# CANTRICK_PERIPHERAL.net
KiCad netlist of a schematic drawn in Altium Designer
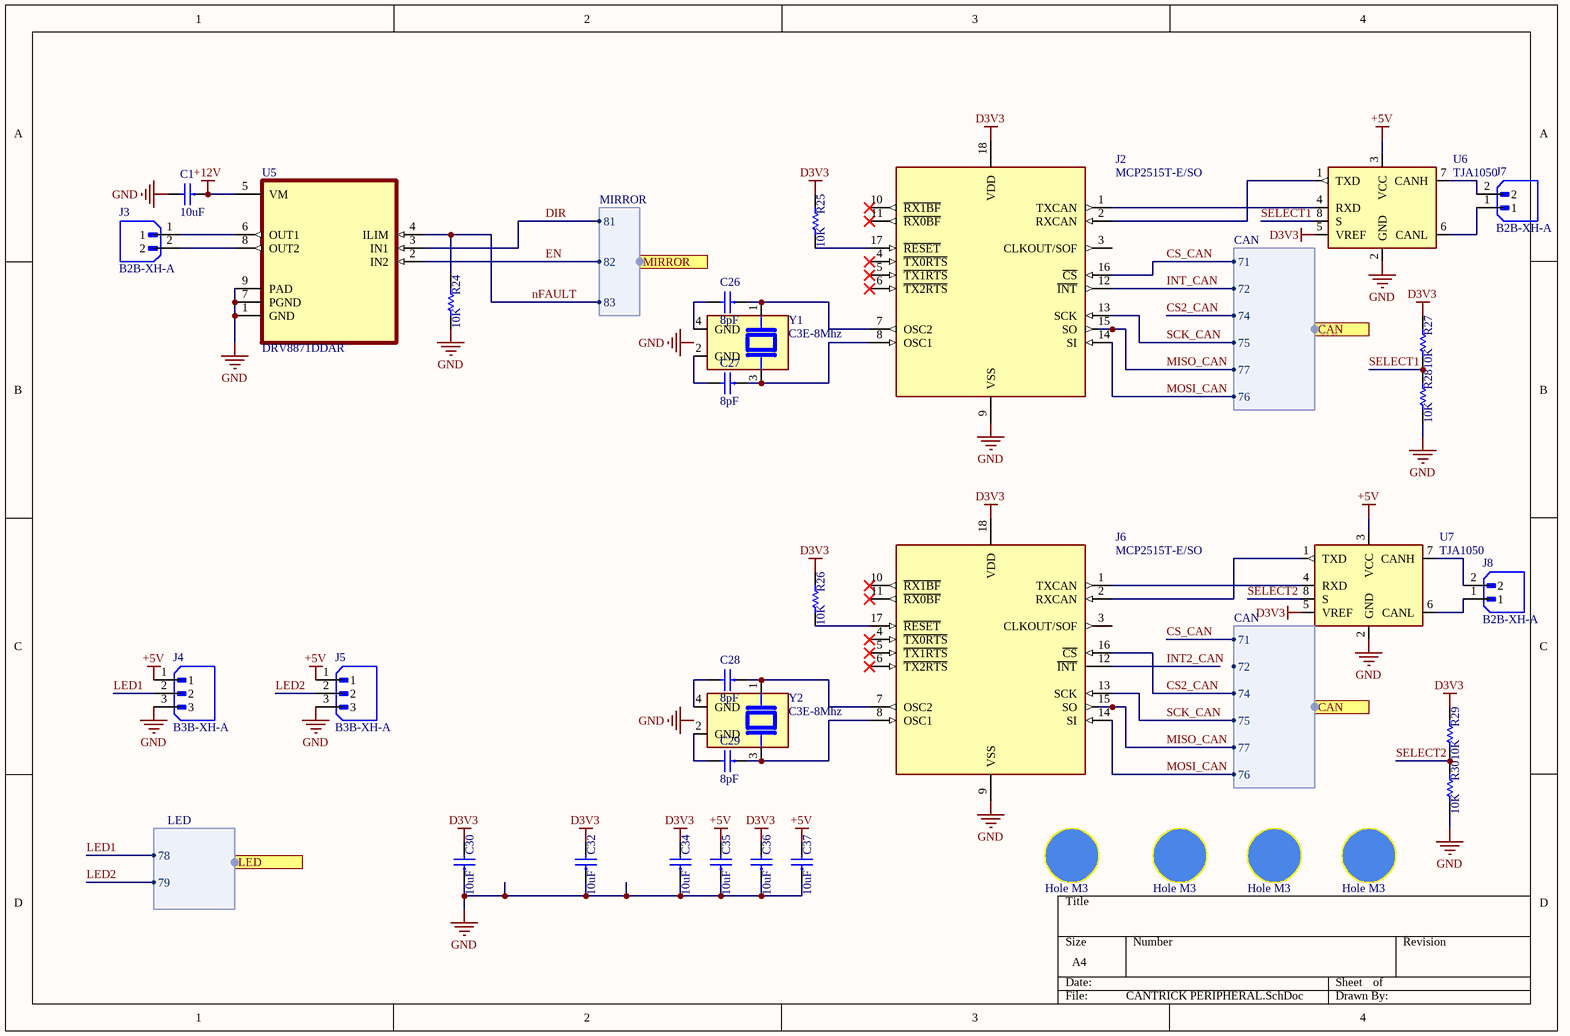
[diagram p0: CANTRICK PERIPHERAL.SchDoc]

(export (version "E")
  (design (tool "Eeschema 10.0.6"))
  (components
    (comp (ref "*1") (value "Hole M3") (footprint "M3") (libsource (lib "POWER_PIN_CAMERA") (part "Hole M3")))
    (comp (ref "*2") (value "Hole M3") (footprint "M3") (libsource (lib "POWER_PIN_CAMERA") (part "Hole M3")))
    (comp (ref "*3") (value "Hole M3") (footprint "M3") (libsource (lib "POWER_PIN_CAMERA") (part "Hole M3")))
    (comp (ref "*4") (value "Hole M3") (footprint "M3") (libsource (lib "POWER_PIN_CAMERA") (part "Hole M3")))
    (comp (ref "C1")
      (value "10uF")
      (footprint "CAP-CER0603-0.8H")
      (description "CAP CER 100nF 10% 50V X7R 0603 SMD")
      (libsource (lib "NAVIGATION") (part "CAPCER0001 100nF 10% 50V X7R 0603 SMD"))
    )
    (comp (ref "C26")
      (value "8pF")
      (footprint "CAP-CER0402-0.5H")
      (description "CAP CER 100nF 10% 50V X7R 0402 SMD")
      (libsource (lib "2502-GMQLITE-MAIN") (part "CAPCER0013 100nF 10% 50V X7R 0402 SMD"))
    )
    (comp (ref "C27")
      (value "8pF")
      (footprint "CAP-CER0402-0.5H")
      (description "CAP CER 100nF 10% 50V X7R 0402 SMD")
      (libsource (lib "2502-GMQLITE-MAIN") (part "CAPCER0013 100nF 10% 50V X7R 0402 SMD"))
    )
    (comp (ref "C28")
      (value "8pF")
      (footprint "CAP-CER0402-0.5H")
      (description "CAP CER 100nF 10% 50V X7R 0402 SMD")
      (libsource (lib "2502-GMQLITE-MAIN") (part "CAPCER0013 100nF 10% 50V X7R 0402 SMD"))
    )
    (comp (ref "C29")
      (value "8pF")
      (footprint "CAP-CER0402-0.5H")
      (description "CAP CER 100nF 10% 50V X7R 0402 SMD")
      (libsource (lib "2502-GMQLITE-MAIN") (part "CAPCER0013 100nF 10% 50V X7R 0402 SMD"))
    )
    (comp (ref "C30")
      (value "10uF")
      (footprint "CAP-CER0603-0.8H")
      (description "CAP CER 100nF 10% 50V X7R 0603 SMD")
      (libsource (lib "NAVIGATION") (part "CAPCER0001 100nF 10% 50V X7R 0603 SMD"))
    )
    (comp (ref "C32")
      (value "10uF")
      (footprint "CAP-CER0603-0.8H")
      (description "CAP CER 100nF 10% 50V X7R 0603 SMD")
      (libsource (lib "NAVIGATION") (part "CAPCER0001 100nF 10% 50V X7R 0603 SMD"))
    )
    (comp (ref "C34")
      (value "10uF")
      (footprint "CAP-CER0603-0.8H")
      (description "CAP CER 100nF 10% 50V X7R 0603 SMD")
      (libsource (lib "NAVIGATION") (part "CAPCER0001 100nF 10% 50V X7R 0603 SMD"))
    )
    (comp (ref "C35")
      (value "10uF")
      (footprint "CAP-CER0603-0.8H")
      (description "CAP CER 100nF 10% 50V X7R 0603 SMD")
      (libsource (lib "NAVIGATION") (part "CAPCER0001 100nF 10% 50V X7R 0603 SMD"))
    )
    (comp (ref "C36")
      (value "10uF")
      (footprint "CAP-CER0603-0.8H")
      (description "CAP CER 100nF 10% 50V X7R 0603 SMD")
      (libsource (lib "NAVIGATION") (part "CAPCER0001 100nF 10% 50V X7R 0603 SMD"))
    )
    (comp (ref "C37")
      (value "10uF")
      (footprint "CAP-CER0603-0.8H")
      (description "CAP CER 100nF 10% 50V X7R 0603 SMD")
      (libsource (lib "NAVIGATION") (part "CAPCER0001 100nF 10% 50V X7R 0603 SMD"))
    )
    (comp (ref "J2")
      (value "MCP2515T-E/SO")
      (footprint "SOIC127P1030X265-18N")
      (fields (field (name "MF") "Microchip"))
      (libsource (lib "MCP2515T-E_SO") (part "MCP2515T-E/SO"))
    )
    (comp (ref "J3")
      (value "B2B-XH-A")
      (footprint "JST_B2B-XH-A")
      (fields (field (name "MF") "{'manufacturer': u'JST Sales America Inc.'}"))
      (libsource (lib "") (part "B2B-XH-A_1"))
    )
    (comp (ref "J4")
      (value "B3B-XH-A")
      (footprint "JST_B3B-XH-A")
      (description "Connector Header Through Hole 3 position 0.098 (2.50mm)")
      (fields (field (name "MF") "JST Sales"))
      (libsource (lib "B3B-XH-A") (part "B3B-XH-A"))
    )
    (comp (ref "J5")
      (value "B3B-XH-A")
      (footprint "JST_B3B-XH-A")
      (description "Connector Header Through Hole 3 position 0.098 (2.50mm)")
      (fields (field (name "MF") "JST Sales"))
      (libsource (lib "B3B-XH-A") (part "B3B-XH-A"))
    )
    (comp (ref "J6")
      (value "MCP2515T-E/SO")
      (footprint "SOIC127P1030X265-18N")
      (fields (field (name "MF") "Microchip"))
      (libsource (lib "MCP2515T-E_SO") (part "MCP2515T-E/SO"))
    )
    (comp (ref "J7")
      (value "B2B-XH-A")
      (footprint "JST_B2B-XH-A")
      (fields (field (name "MF") "{'manufacturer': u'JST Sales America Inc.'}"))
      (libsource (lib "B2B-XH-A") (part "B2B-XH-A"))
    )
    (comp (ref "J8")
      (value "B2B-XH-A")
      (footprint "JST_B2B-XH-A")
      (fields (field (name "MF") "{'manufacturer': u'JST Sales America Inc.'}"))
      (libsource (lib "B2B-XH-A") (part "B2B-XH-A"))
    )
    (comp (ref "R24")
      (value "10K")
      (footprint "Res 0603")
      (description "Res Thick Film 0603 2.2K Ohm 5% 1/10W ±200ppm/°C Molded SMD SMD Paper T/R")
      (fields
        (field (name "MANUFACTURER") "Vishay")
        (field (name "MANUFACTURER PART NUMBER") "CRCW06032K20JNEA")
      )
      (libsource (lib "Stm32_Flyback_Driver_250814_1") (part "Resistor 2.2K"))
    )
    (comp (ref "R25")
      (value "10K")
      (footprint "Res 0603")
      (description "Res Thick Film 0603 2.2K Ohm 5% 1/10W ±200ppm/°C Molded SMD SMD Paper T/R")
      (fields
        (field (name "MANUFACTURER") "Vishay")
        (field (name "MANUFACTURER PART NUMBER") "CRCW06032K20JNEA")
      )
      (libsource (lib "Stm32_Flyback_Driver_250814_1") (part "Resistor 2.2K"))
    )
    (comp (ref "R26")
      (value "10K")
      (footprint "Res 0603")
      (description "Res Thick Film 0603 2.2K Ohm 5% 1/10W ±200ppm/°C Molded SMD SMD Paper T/R")
      (fields
        (field (name "MANUFACTURER") "Vishay")
        (field (name "MANUFACTURER PART NUMBER") "CRCW06032K20JNEA")
      )
      (libsource (lib "Stm32_Flyback_Driver_250814_1") (part "Resistor 2.2K"))
    )
    (comp (ref "R27")
      (value "10K")
      (footprint "Res 0603")
      (description "Res Thick Film 0603 2.2K Ohm 5% 1/10W ±200ppm/°C Molded SMD SMD Paper T/R")
      (fields
        (field (name "MANUFACTURER") "Vishay")
        (field (name "MANUFACTURER PART NUMBER") "CRCW06032K20JNEA")
      )
      (libsource (lib "Stm32_Flyback_Driver_250814_1") (part "Resistor 2.2K"))
    )
    (comp (ref "R28")
      (value "10K")
      (footprint "Res 0603")
      (description "Res Thick Film 0603 2.2K Ohm 5% 1/10W ±200ppm/°C Molded SMD SMD Paper T/R")
      (fields
        (field (name "MANUFACTURER") "Vishay")
        (field (name "MANUFACTURER PART NUMBER") "CRCW06032K20JNEA")
      )
      (libsource (lib "Stm32_Flyback_Driver_250814_1") (part "Resistor 2.2K"))
    )
    (comp (ref "R29")
      (value "10K")
      (footprint "Res 0603")
      (description "Res Thick Film 0603 2.2K Ohm 5% 1/10W ±200ppm/°C Molded SMD SMD Paper T/R")
      (fields
        (field (name "MANUFACTURER") "Vishay")
        (field (name "MANUFACTURER PART NUMBER") "CRCW06032K20JNEA")
      )
      (libsource (lib "Stm32_Flyback_Driver_250814_1") (part "Resistor 2.2K"))
    )
    (comp (ref "R30")
      (value "10K")
      (footprint "Res 0603")
      (description "Res Thick Film 0603 2.2K Ohm 5% 1/10W ±200ppm/°C Molded SMD SMD Paper T/R")
      (fields
        (field (name "MANUFACTURER") "Vishay")
        (field (name "MANUFACTURER PART NUMBER") "CRCW06032K20JNEA")
      )
      (libsource (lib "Stm32_Flyback_Driver_250814_1") (part "Resistor 2.2K"))
    )
    (comp (ref "U5")
      (value "DRV8871DDAR")
      (footprint "VREG_LM5017MR/NOPB")
      (description "50-V, 3.6-A H-bridge motor driver with integrated current sensing")
      (fields (field (name "MF") "Texas Instruments"))
      (libsource (lib "DRV8871DDAR") (part "DRV8871DDAR"))
    )
    (comp (ref "U6")
      (value "TJA1050")
      (footprint "SOT96-1")
      (description "CAN 1MBd Silent 5V Automotive 8-Pin SO T/R")
      (fields (field (name "MF") "NXP Semiconductors"))
      (libsource (lib "TJA1050") (part "TJA1050"))
    )
    (comp (ref "U7")
      (value "TJA1050")
      (footprint "SOT96-1")
      (description "CAN 1MBd Silent 5V Automotive 8-Pin SO T/R")
      (fields (field (name "MF") "NXP Semiconductors"))
      (libsource (lib "TJA1050") (part "TJA1050"))
    )
    (comp (ref "Y1")
      (value "C3E-8Mhz")
      (footprint "XTAL_C3E-8.000-8-1015-R")
      (fields (field (name "MP") "C3E-8.000-8-1015-R"))
      (libsource (lib "C3E-8.000-8-1015-R") (part "C3E-8.000-8-1015-R"))
    )
    (comp (ref "Y2")
      (value "C3E-8Mhz")
      (footprint "XTAL_C3E-8.000-8-1015-R")
      (fields (field (name "MP") "C3E-8.000-8-1015-R"))
      (libsource (lib "C3E-8.000-8-1015-R") (part "C3E-8.000-8-1015-R"))
    )
  )
  (nets
    (net (code "4") (name "+5V") (class "Default")
      (node (ref "C35") (pin "2") (pinfunction "2_2") (pintype "passive"))
      (node (ref "C37") (pin "2") (pinfunction "2_2") (pintype "passive"))
      (node (ref "J4") (pin "1") (pinfunction "1_1") (pintype "passive"))
      (node (ref "J5") (pin "1") (pinfunction "1_1") (pintype "passive"))
      (node (ref "U6") (pin "3") (pinfunction "VCC_3") (pintype "bidirectional"))
      (node (ref "U7") (pin "3") (pinfunction "VCC_3") (pintype "bidirectional"))
    )
    (net (code "5") (name "+12V") (class "Default")
      (node (ref "C1") (pin "1") (pinfunction "1_1") (pintype "passive"))
      (node (ref "U5") (pin "5") (pinfunction "VM_5") (pintype "power_in"))
    )
    (net (code "6") (name "/CS2_CAN") (class "Default")
      (node (ref "J6") (pin "16") (pinfunction "~{CS}_16") (pintype "input"))
    )
    (net (code "7") (name "/CS_CAN") (class "Default")
      (node (ref "J2") (pin "16") (pinfunction "~{CS}_16") (pintype "input"))
    )
    (net (code "8") (name "/DIR") (class "Default")
      (node (ref "U5") (pin "3") (pinfunction "IN1_3") (pintype "input"))
    )
    (net (code "9") (name "/EN") (class "Default")
      (node (ref "U5") (pin "2") (pinfunction "IN2_2") (pintype "input"))
    )
    (net (code "10") (name "/INT2_CAN") (class "Default")
      (node (ref "J6") (pin "12") (pinfunction "~{INT}_12") (pintype "output"))
    )
    (net (code "11") (name "/INT_CAN") (class "Default")
      (node (ref "J2") (pin "12") (pinfunction "~{INT}_12") (pintype "output"))
    )
    (net (code "12") (name "/LED1") (class "Default")
      (node (ref "J4") (pin "2") (pinfunction "2_2") (pintype "passive"))
    )
    (net (code "13") (name "/LED2") (class "Default")
      (node (ref "J5") (pin "2") (pinfunction "2_2") (pintype "passive"))
    )
    (net (code "14") (name "/MISO_CAN") (class "Default")
      (node (ref "J2") (pin "15") (pinfunction "SO_15") (pintype "output"))
      (node (ref "J6") (pin "15") (pinfunction "SO_15") (pintype "output"))
    )
    (net (code "15") (name "/MOSI_CAN") (class "Default")
      (node (ref "J2") (pin "14") (pinfunction "SI_14") (pintype "input"))
      (node (ref "J6") (pin "14") (pinfunction "SI_14") (pintype "input"))
    )
    (net (code "16") (name "/SCK_CAN") (class "Default")
      (node (ref "J2") (pin "13") (pinfunction "SCK_13") (pintype "input"))
      (node (ref "J6") (pin "13") (pinfunction "SCK_13") (pintype "input"))
    )
    (net (code "17") (name "/SELECT1") (class "Default")
      (node (ref "R27") (pin "1") (pinfunction "1_1") (pintype "passive"))
      (node (ref "R28") (pin "2") (pinfunction "2_2") (pintype "passive"))
      (node (ref "U6") (pin "8") (pinfunction "S_8") (pintype "power_in"))
    )
    (net (code "18") (name "/SELECT2") (class "Default")
      (node (ref "R29") (pin "1") (pinfunction "1_1") (pintype "passive"))
      (node (ref "R30") (pin "2") (pinfunction "2_2") (pintype "passive"))
      (node (ref "U7") (pin "8") (pinfunction "S_8") (pintype "power_in"))
    )
    (net (code "19") (name "/nFAULT") (class "Default")
      (node (ref "R24") (pin "2") (pinfunction "2_2") (pintype "passive"))
      (node (ref "U5") (pin "4") (pinfunction "ILIM_4") (pintype "input"))
    )
    (net (code "23") (name "D3V3") (class "Default")
      (node (ref "C30") (pin "2") (pinfunction "2_2") (pintype "passive"))
      (node (ref "C32") (pin "2") (pinfunction "2_2") (pintype "passive"))
      (node (ref "C34") (pin "2") (pinfunction "2_2") (pintype "passive"))
      (node (ref "C36") (pin "2") (pinfunction "2_2") (pintype "passive"))
      (node (ref "J2") (pin "18") (pinfunction "VDD_18") (pintype "power_in"))
      (node (ref "J6") (pin "18") (pinfunction "VDD_18") (pintype "power_in"))
      (node (ref "R25") (pin "2") (pinfunction "2_2") (pintype "passive"))
      (node (ref "R26") (pin "2") (pinfunction "2_2") (pintype "passive"))
      (node (ref "R27") (pin "2") (pinfunction "2_2") (pintype "passive"))
      (node (ref "R29") (pin "2") (pinfunction "2_2") (pintype "passive"))
      (node (ref "U6") (pin "5") (pinfunction "VREF_5") (pintype "passive"))
      (node (ref "U7") (pin "5") (pinfunction "VREF_5") (pintype "passive"))
    )
    (net (code "24") (name "GND") (class "Default")
      (node (ref "C1") (pin "2") (pinfunction "2_2") (pintype "passive"))
      (node (ref "C30") (pin "1") (pinfunction "1_1") (pintype "passive"))
      (node (ref "C32") (pin "1") (pinfunction "1_1") (pintype "passive"))
      (node (ref "C34") (pin "1") (pinfunction "1_1") (pintype "passive"))
      (node (ref "C35") (pin "1") (pinfunction "1_1") (pintype "passive"))
      (node (ref "C36") (pin "1") (pinfunction "1_1") (pintype "passive"))
      (node (ref "C37") (pin "1") (pinfunction "1_1") (pintype "passive"))
      (node (ref "J2") (pin "9") (pinfunction "VSS_9") (pintype "power_in"))
      (node (ref "J4") (pin "3") (pinfunction "3_3") (pintype "passive"))
      (node (ref "J5") (pin "3") (pinfunction "3_3") (pintype "passive"))
      (node (ref "J6") (pin "9") (pinfunction "VSS_9") (pintype "power_in"))
      (node (ref "R24") (pin "1") (pinfunction "1_1") (pintype "passive"))
      (node (ref "R28") (pin "1") (pinfunction "1_1") (pintype "passive"))
      (node (ref "R30") (pin "1") (pinfunction "1_1") (pintype "passive"))
      (node (ref "U5") (pin "1") (pinfunction "GND_1") (pintype "power_in"))
      (node (ref "U5") (pin "7") (pinfunction "PGND_7") (pintype "power_in"))
      (node (ref "U5") (pin "9") (pinfunction "PAD_9") (pintype "power_in"))
      (node (ref "U6") (pin "2") (pinfunction "GND_2") (pintype "bidirectional"))
      (node (ref "U7") (pin "2") (pinfunction "GND_2") (pintype "bidirectional"))
    )
    (net (code "25") (name "Net-(C26-Pad2)") (class "Default")
      (node (ref "C26") (pin "2") (pinfunction "2_2") (pintype "passive"))
      (node (ref "Y1") (pin "4") (pinfunction "GND_4") (pintype "power_in"))
    )
    (net (code "26") (name "Net-(C27-Pad2)") (class "Default")
      (node (ref "C27") (pin "2") (pinfunction "2_2") (pintype "passive"))
      (node (ref "Y1") (pin "2") (pinfunction "GND_2") (pintype "power_in"))
    )
    (net (code "27") (name "Net-(C28-Pad2)") (class "Default")
      (node (ref "C28") (pin "2") (pinfunction "2_2") (pintype "passive"))
      (node (ref "Y2") (pin "4") (pinfunction "GND_4") (pintype "power_in"))
    )
    (net (code "28") (name "Net-(C29-Pad2)") (class "Default")
      (node (ref "C29") (pin "2") (pinfunction "2_2") (pintype "passive"))
      (node (ref "Y2") (pin "2") (pinfunction "GND_2") (pintype "power_in"))
    )
    (net (code "29") (name "Net-(J2-OSC1)") (class "Default")
      (node (ref "C27") (pin "1") (pinfunction "1_1") (pintype "passive"))
      (node (ref "J2") (pin "8") (pinfunction "OSC1_8") (pintype "input"))
      (node (ref "Y1") (pin "3") (pinfunction "2_3") (pintype "passive"))
    )
    (net (code "30") (name "Net-(J2-OSC2)") (class "Default")
      (node (ref "C26") (pin "1") (pinfunction "1_1") (pintype "passive"))
      (node (ref "J2") (pin "7") (pinfunction "OSC2_7") (pintype "output"))
      (node (ref "Y1") (pin "1") (pinfunction "1_1") (pintype "passive"))
    )
    (net (code "31") (name "Net-(J2-RXCAN)") (class "Default")
      (node (ref "J2") (pin "2") (pinfunction "RXCAN_2") (pintype "input"))
      (node (ref "U6") (pin "1") (pinfunction "TXD_1") (pintype "output"))
    )
    (net (code "32") (name "Net-(J2-TXCAN)") (class "Default")
      (node (ref "J2") (pin "1") (pinfunction "TXCAN_1") (pintype "output"))
      (node (ref "U6") (pin "4") (pinfunction "RXD_4") (pintype "bidirectional"))
    )
    (net (code "33") (name "Net-(J2-~{RESET})") (class "Default")
      (node (ref "J2") (pin "17") (pinfunction "~{RESET}_17") (pintype "input"))
      (node (ref "R25") (pin "1") (pinfunction "1_1") (pintype "passive"))
    )
    (net (code "34") (name "Net-(J6-OSC1)") (class "Default")
      (node (ref "C29") (pin "1") (pinfunction "1_1") (pintype "passive"))
      (node (ref "J6") (pin "8") (pinfunction "OSC1_8") (pintype "input"))
      (node (ref "Y2") (pin "3") (pinfunction "2_3") (pintype "passive"))
    )
    (net (code "35") (name "Net-(J6-OSC2)") (class "Default")
      (node (ref "C28") (pin "1") (pinfunction "1_1") (pintype "passive"))
      (node (ref "J6") (pin "7") (pinfunction "OSC2_7") (pintype "output"))
      (node (ref "Y2") (pin "1") (pinfunction "1_1") (pintype "passive"))
    )
    (net (code "36") (name "Net-(J6-RXCAN)") (class "Default")
      (node (ref "J6") (pin "2") (pinfunction "RXCAN_2") (pintype "input"))
      (node (ref "U7") (pin "1") (pinfunction "TXD_1") (pintype "output"))
    )
    (net (code "37") (name "Net-(J6-TXCAN)") (class "Default")
      (node (ref "J6") (pin "1") (pinfunction "TXCAN_1") (pintype "output"))
      (node (ref "U7") (pin "4") (pinfunction "RXD_4") (pintype "bidirectional"))
    )
    (net (code "38") (name "Net-(J6-~{RESET})") (class "Default")
      (node (ref "J6") (pin "17") (pinfunction "~{RESET}_17") (pintype "input"))
      (node (ref "R26") (pin "1") (pinfunction "1_1") (pintype "passive"))
    )
    (net (code "39") (name "Net-(U5-OUT1)") (class "Default")
      (node (ref "J3") (pin "1") (pinfunction "1_1") (pintype "passive"))
      (node (ref "U5") (pin "6") (pinfunction "OUT1_6") (pintype "output"))
    )
    (net (code "40") (name "Net-(U5-OUT2)") (class "Default")
      (node (ref "J3") (pin "2") (pinfunction "2_2") (pintype "passive"))
      (node (ref "U5") (pin "8") (pinfunction "OUT2_8") (pintype "output"))
    )
    (net (code "41") (name "Net-(U6-CANH)") (class "Default")
      (node (ref "J7") (pin "2") (pinfunction "2_2") (pintype "passive"))
      (node (ref "U6") (pin "7") (pinfunction "CANH_7") (pintype "bidirectional"))
    )
    (net (code "42") (name "Net-(U6-CANL)") (class "Default")
      (node (ref "J7") (pin "1") (pinfunction "1_1") (pintype "passive"))
      (node (ref "U6") (pin "6") (pinfunction "CANL_6") (pintype "bidirectional"))
    )
    (net (code "43") (name "Net-(U7-CANH)") (class "Default")
      (node (ref "J8") (pin "2") (pinfunction "2_2") (pintype "passive"))
      (node (ref "U7") (pin "7") (pinfunction "CANH_7") (pintype "bidirectional"))
    )
    (net (code "44") (name "Net-(U7-CANL)") (class "Default")
      (node (ref "J8") (pin "1") (pinfunction "1_1") (pintype "passive"))
      (node (ref "U7") (pin "6") (pinfunction "CANL_6") (pintype "bidirectional"))
    )
    (net (code "45") (name "unconnected-(J2-CLKOUT{slash}SOF-Pad3)") (class "Default")
      (node (ref "J2") (pin "3") (pinfunction "CLKOUT/SOF_3") (pintype "output"))
    )
    (net (code "46") (name "unconnected-(J2-~{RX0BF}-Pad11)") (class "Default")
      (node (ref "J2") (pin "11") (pinfunction "~{RX0BF}_11") (pintype "output+no_connect"))
    )
    (net (code "47") (name "unconnected-(J2-~{RX1BF}-Pad10)") (class "Default")
      (node (ref "J2") (pin "10") (pinfunction "~{RX1BF}_10") (pintype "output+no_connect"))
    )
    (net (code "48") (name "unconnected-(J2-~{TX0RTS}-Pad4)") (class "Default")
      (node (ref "J2") (pin "4") (pinfunction "~{TX0RTS}_4") (pintype "input+no_connect"))
    )
    (net (code "49") (name "unconnected-(J2-~{TX1RTS}-Pad5)") (class "Default")
      (node (ref "J2") (pin "5") (pinfunction "~{TX1RTS}_5") (pintype "input+no_connect"))
    )
    (net (code "50") (name "unconnected-(J2-~{TX2RTS}-Pad6)") (class "Default")
      (node (ref "J2") (pin "6") (pinfunction "~{TX2RTS}_6") (pintype "input+no_connect"))
    )
    (net (code "51") (name "unconnected-(J6-CLKOUT{slash}SOF-Pad3)") (class "Default")
      (node (ref "J6") (pin "3") (pinfunction "CLKOUT/SOF_3") (pintype "output"))
    )
    (net (code "52") (name "unconnected-(J6-~{RX0BF}-Pad11)") (class "Default")
      (node (ref "J6") (pin "11") (pinfunction "~{RX0BF}_11") (pintype "output+no_connect"))
    )
    (net (code "53") (name "unconnected-(J6-~{RX1BF}-Pad10)") (class "Default")
      (node (ref "J6") (pin "10") (pinfunction "~{RX1BF}_10") (pintype "output+no_connect"))
    )
    (net (code "54") (name "unconnected-(J6-~{TX0RTS}-Pad4)") (class "Default")
      (node (ref "J6") (pin "4") (pinfunction "~{TX0RTS}_4") (pintype "input+no_connect"))
    )
    (net (code "55") (name "unconnected-(J6-~{TX1RTS}-Pad5)") (class "Default")
      (node (ref "J6") (pin "5") (pinfunction "~{TX1RTS}_5") (pintype "input+no_connect"))
    )
    (net (code "56") (name "unconnected-(J6-~{TX2RTS}-Pad6)") (class "Default")
      (node (ref "J6") (pin "6") (pinfunction "~{TX2RTS}_6") (pintype "input+no_connect"))
    )
  )
)
